# Sheet1.net
KiCad netlist of a schematic drawn in Altium Designer
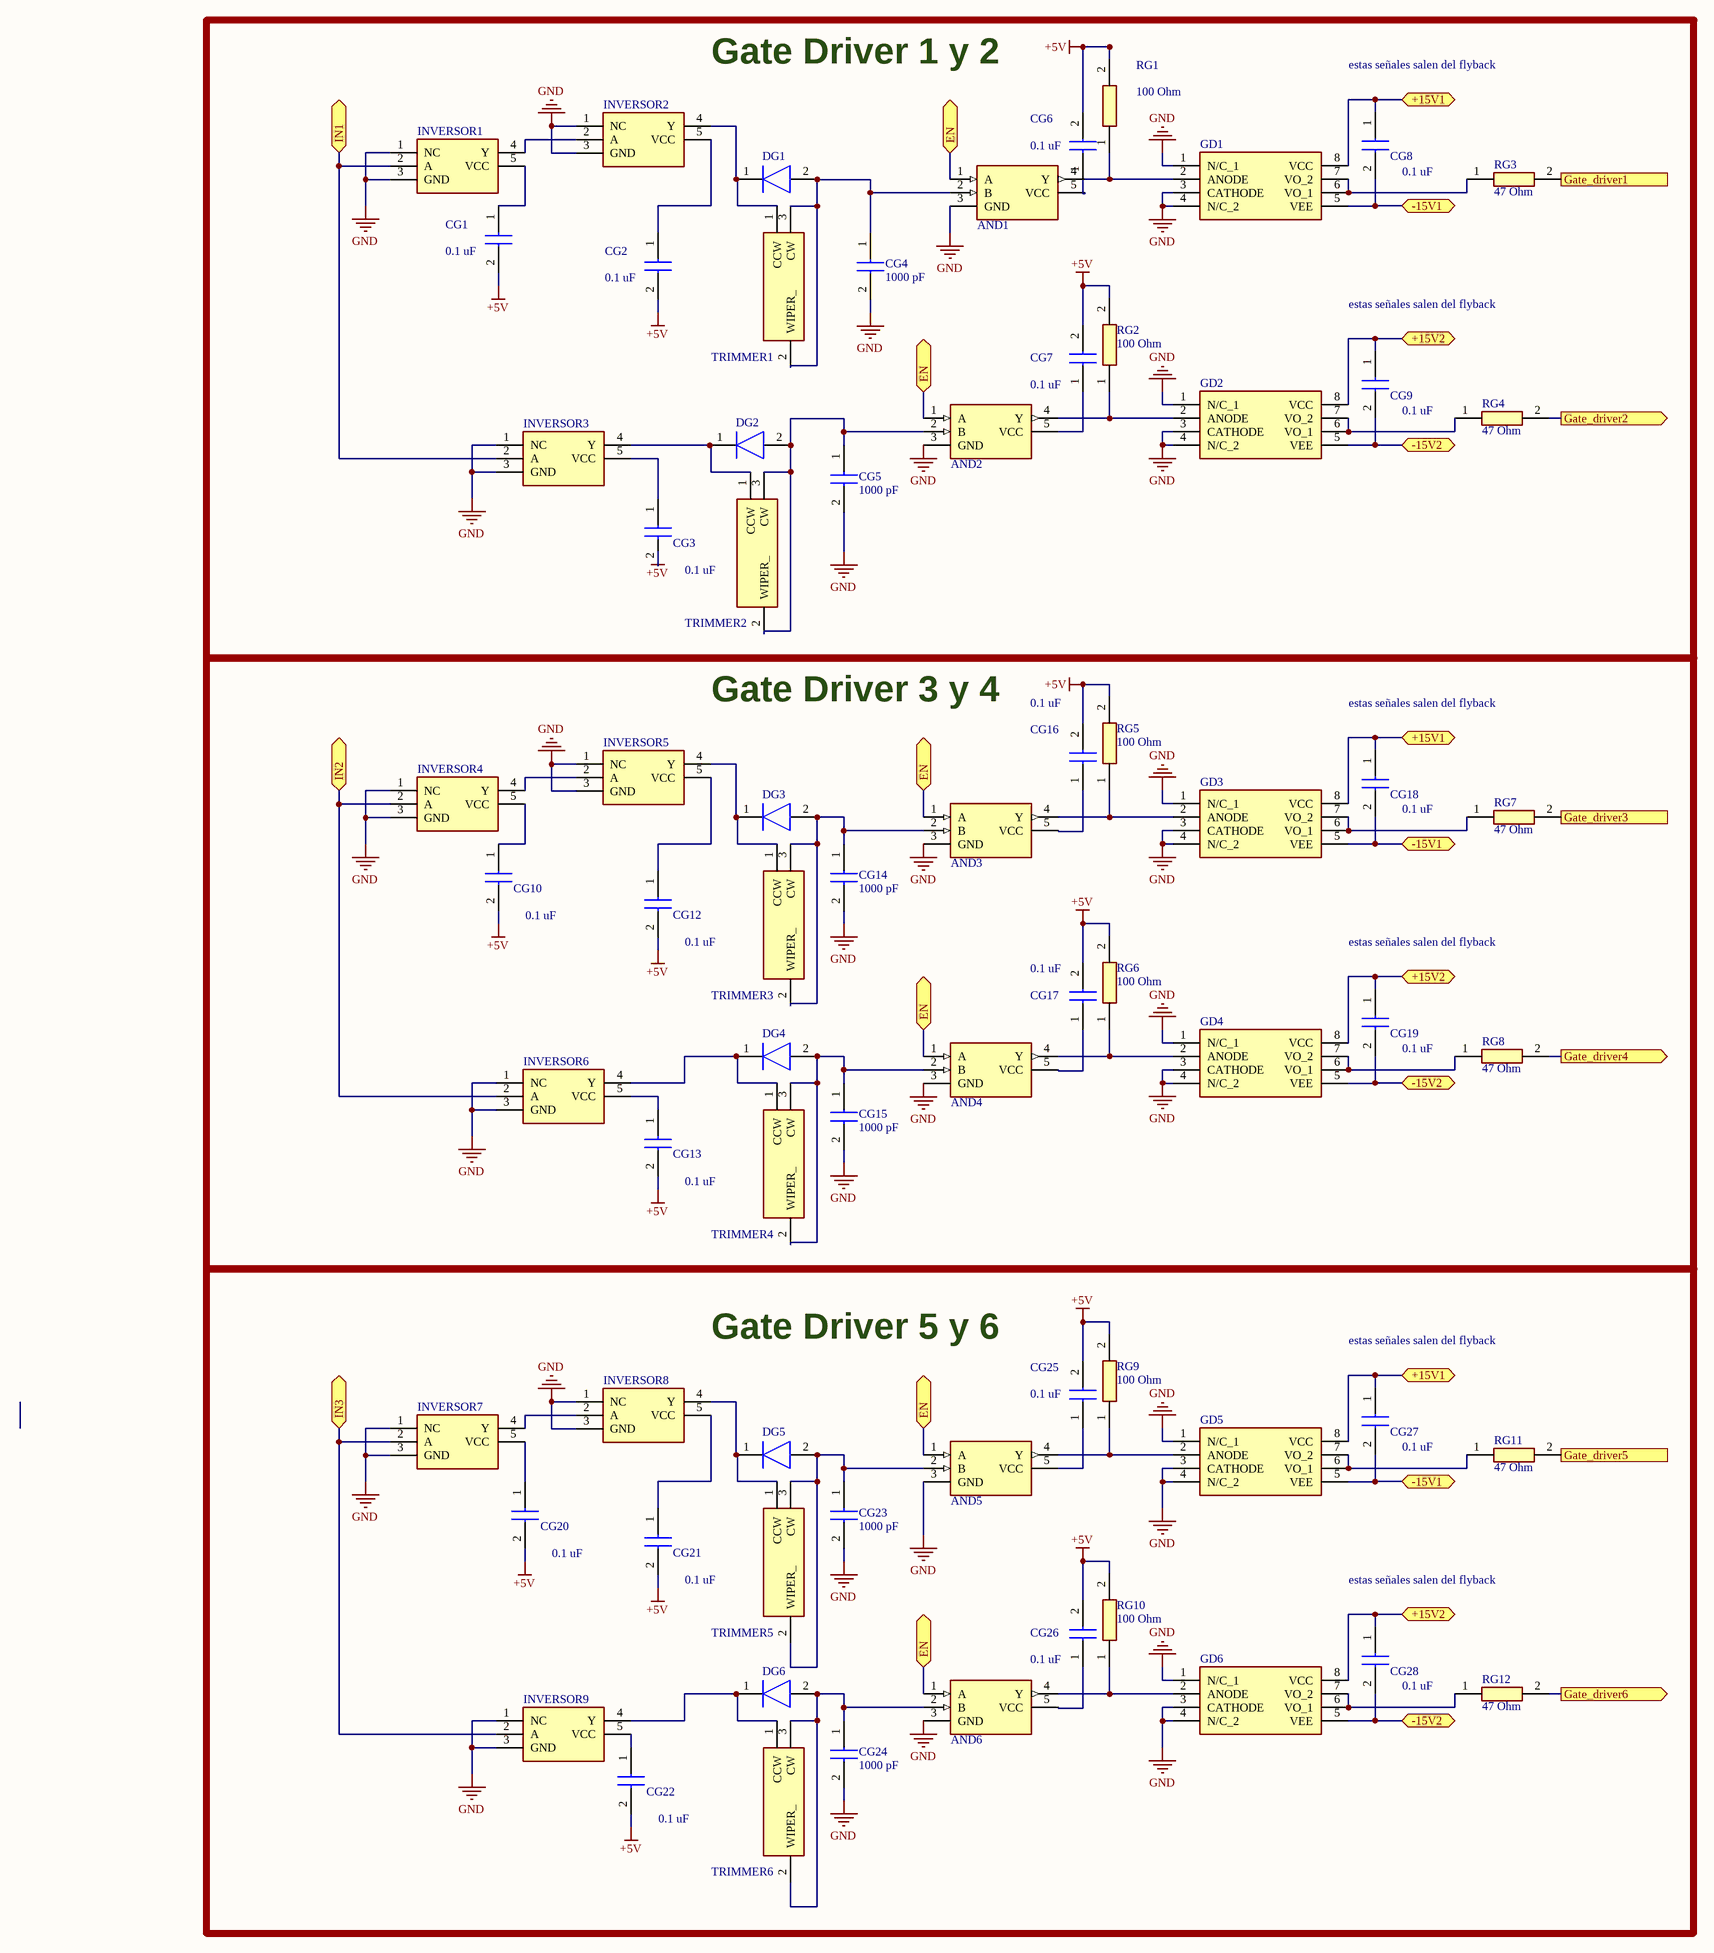
[diagram p0: Sheet1.SchDoc]

(export (version "E")
  (design (tool "Eeschema 10.0.6"))
  (components
    (comp (ref "AND1")
      (value "SN74AHC1G09DCKR")
      (footprint "jasiel:SOT65P210X110-5N")
      (fields (field (name "MANUFACTURER") "Texas Instruments"))
      (libsource (lib "sch jasiel") (part "SN74AHC1G09DCKR"))
    )
    (comp (ref "AND2")
      (value "SN74AHC1G09DCKR")
      (footprint "jasiel:SOT65P210X110-5N")
      (fields (field (name "MANUFACTURER") "Texas Instruments"))
      (libsource (lib "sch jasiel") (part "SN74AHC1G09DCKR"))
    )
    (comp (ref "AND3")
      (value "SN74AHC1G09DCKR")
      (footprint "jasiel:SOT65P210X110-5N")
      (fields (field (name "MANUFACTURER") "Texas Instruments"))
      (libsource (lib "sch jasiel") (part "SN74AHC1G09DCKR"))
    )
    (comp (ref "AND4")
      (value "SN74AHC1G09DCKR")
      (footprint "jasiel:SOT65P210X110-5N")
      (fields (field (name "MANUFACTURER") "Texas Instruments"))
      (libsource (lib "sch jasiel") (part "SN74AHC1G09DCKR"))
    )
    (comp (ref "AND5")
      (value "SN74AHC1G09DCKR")
      (footprint "jasiel:SOT65P210X110-5N")
      (fields (field (name "MANUFACTURER") "Texas Instruments"))
      (libsource (lib "sch jasiel") (part "SN74AHC1G09DCKR"))
    )
    (comp (ref "AND6")
      (value "SN74AHC1G09DCKR")
      (footprint "jasiel:SOT65P210X110-5N")
      (fields (field (name "MANUFACTURER") "Texas Instruments"))
      (libsource (lib "sch jasiel") (part "SN74AHC1G09DCKR"))
    )
    (comp (ref "CG1")
      (value "0.1 uF")
      (footprint "SamacSys:CAPC2012X94N")
      (description "Multilayer Ceramic Capacitors MLCC - SMD/SMT 16V .1uF X7R 0805 10%")
      (fields
        (field (name "MANUFACTURER_PART_NUMBER") "0805YC104KAT2A")
        (field (name "MOUSER PART NUMBER") "581-0805YC104K")
      )
      (libsource (lib "*") (part "0805YC104KAT2A"))
    )
    (comp (ref "CG2")
      (value "0.1 uF")
      (footprint "SamacSys:CAPC2012X94N")
      (description "Multilayer Ceramic Capacitors MLCC - SMD/SMT 16V .1uF X7R 0805 10%")
      (fields
        (field (name "MANUFACTURER_PART_NUMBER") "0805YC104KAT2A")
        (field (name "MOUSER PART NUMBER") "581-0805YC104K")
      )
      (libsource (lib "*") (part "0805YC104KAT2A"))
    )
    (comp (ref "CG3")
      (value "0.1 uF")
      (footprint "SamacSys:CAPC2012X94N")
      (description "Multilayer Ceramic Capacitors MLCC - SMD/SMT 16V .1uF X7R 0805 10%")
      (fields
        (field (name "MANUFACTURER_PART_NUMBER") "0805YC104KAT2A")
        (field (name "MOUSER PART NUMBER") "581-0805YC104K")
      )
      (libsource (lib "*") (part "0805YC104KAT2A"))
    )
    (comp (ref "CG4")
      (value "1000 pF")
      (footprint "SamacSys:CAPC2012X98N")
      (description "Multilayer Ceramic Capacitors MLCC - SMD/SMT 25volts 1000pF 10% X7R")
      (fields
        (field (name "MANUFACTURER_PART_NUMBER") "C0805Y102K3RACTU")
        (field (name "MOUSER PART NUMBER") "80-C0805Y102K3R")
      )
      (libsource (lib "sch jasiel") (part "C0805Y102K3RACTU"))
    )
    (comp (ref "CG5")
      (value "1000 pF")
      (footprint "SamacSys:CAPC2012X98N")
      (description "Multilayer Ceramic Capacitors MLCC - SMD/SMT 25volts 1000pF 10% X7R")
      (fields
        (field (name "MANUFACTURER_PART_NUMBER") "C0805Y102K3RACTU")
        (field (name "MOUSER PART NUMBER") "80-C0805Y102K3R")
      )
      (libsource (lib "sch jasiel") (part "C0805Y102K3RACTU"))
    )
    (comp (ref "CG6")
      (value "0.1 uF")
      (footprint "SamacSys:CAPC2012X94N")
      (description "Multilayer Ceramic Capacitors MLCC - SMD/SMT 16V .1uF X7R 0805 10%")
      (fields
        (field (name "MANUFACTURER_PART_NUMBER") "0805YC104KAT2A")
        (field (name "MOUSER PART NUMBER") "581-0805YC104K")
      )
      (libsource (lib "*") (part "0805YC104KAT2A"))
    )
    (comp (ref "CG7")
      (value "0.1 uF")
      (footprint "SamacSys:CAPC2012X94N")
      (description "Multilayer Ceramic Capacitors MLCC - SMD/SMT 16V .1uF X7R 0805 10%")
      (fields
        (field (name "MANUFACTURER_PART_NUMBER") "0805YC104KAT2A")
        (field (name "MOUSER PART NUMBER") "581-0805YC104K")
      )
      (libsource (lib "*") (part "0805YC104KAT2A"))
    )
    (comp (ref "CG8")
      (value "0.1 uF")
      (footprint "SamacSys:CAPC2012X94N")
      (description "Multilayer Ceramic Capacitors MLCC - SMD/SMT 16V .1uF X7R 0805 10%")
      (fields
        (field (name "MANUFACTURER_PART_NUMBER") "0805YC104KAT2A")
        (field (name "MOUSER PART NUMBER") "581-0805YC104K")
      )
      (libsource (lib "*") (part "0805YC104KAT2A"))
    )
    (comp (ref "CG9")
      (value "0.1 uF")
      (footprint "SamacSys:CAPC2012X94N")
      (description "Multilayer Ceramic Capacitors MLCC - SMD/SMT 16V .1uF X7R 0805 10%")
      (fields
        (field (name "MANUFACTURER_PART_NUMBER") "0805YC104KAT2A")
        (field (name "MOUSER PART NUMBER") "581-0805YC104K")
      )
      (libsource (lib "*") (part "0805YC104KAT2A"))
    )
    (comp (ref "CG10")
      (value "0.1 uF")
      (footprint "SamacSys:CAPC2012X94N")
      (description "Multilayer Ceramic Capacitors MLCC - SMD/SMT 16V .1uF X7R 0805 10%")
      (fields
        (field (name "MANUFACTURER_PART_NUMBER") "0805YC104KAT2A")
        (field (name "MOUSER PART NUMBER") "581-0805YC104K")
      )
      (libsource (lib "*") (part "0805YC104KAT2A"))
    )
    (comp (ref "CG12")
      (value "0.1 uF")
      (footprint "SamacSys:CAPC2012X94N")
      (description "Multilayer Ceramic Capacitors MLCC - SMD/SMT 16V .1uF X7R 0805 10%")
      (fields
        (field (name "MANUFACTURER_PART_NUMBER") "0805YC104KAT2A")
        (field (name "MOUSER PART NUMBER") "581-0805YC104K")
      )
      (libsource (lib "*") (part "0805YC104KAT2A"))
    )
    (comp (ref "CG13")
      (value "0.1 uF")
      (footprint "SamacSys:CAPC2012X94N")
      (description "Multilayer Ceramic Capacitors MLCC - SMD/SMT 16V .1uF X7R 0805 10%")
      (fields
        (field (name "MANUFACTURER_PART_NUMBER") "0805YC104KAT2A")
        (field (name "MOUSER PART NUMBER") "581-0805YC104K")
      )
      (libsource (lib "*") (part "0805YC104KAT2A"))
    )
    (comp (ref "CG14")
      (value "1000 pF")
      (footprint "SamacSys:CAPC2012X98N")
      (description "Multilayer Ceramic Capacitors MLCC - SMD/SMT 25volts 1000pF 10% X7R")
      (fields
        (field (name "MANUFACTURER_PART_NUMBER") "C0805Y102K3RACTU")
        (field (name "MOUSER PART NUMBER") "80-C0805Y102K3R")
      )
      (libsource (lib "sch jasiel") (part "C0805Y102K3RACTU"))
    )
    (comp (ref "CG15")
      (value "1000 pF")
      (footprint "SamacSys:CAPC2012X98N")
      (description "Multilayer Ceramic Capacitors MLCC - SMD/SMT 25volts 1000pF 10% X7R")
      (fields
        (field (name "MANUFACTURER_PART_NUMBER") "C0805Y102K3RACTU")
        (field (name "MOUSER PART NUMBER") "80-C0805Y102K3R")
      )
      (libsource (lib "sch jasiel") (part "C0805Y102K3RACTU"))
    )
    (comp (ref "CG16")
      (value "0.1 uF")
      (footprint "SamacSys:CAPC2012X94N")
      (description "Multilayer Ceramic Capacitors MLCC - SMD/SMT 16V .1uF X7R 0805 10%")
      (fields
        (field (name "MANUFACTURER_PART_NUMBER") "0805YC104KAT2A")
        (field (name "MOUSER PART NUMBER") "581-0805YC104K")
      )
      (libsource (lib "*") (part "0805YC104KAT2A"))
    )
    (comp (ref "CG17")
      (value "0.1 uF")
      (footprint "SamacSys:CAPC2012X94N")
      (description "Multilayer Ceramic Capacitors MLCC - SMD/SMT 16V .1uF X7R 0805 10%")
      (fields
        (field (name "MANUFACTURER_PART_NUMBER") "0805YC104KAT2A")
        (field (name "MOUSER PART NUMBER") "581-0805YC104K")
      )
      (libsource (lib "*") (part "0805YC104KAT2A"))
    )
    (comp (ref "CG18")
      (value "0.1 uF")
      (footprint "SamacSys:CAPC2012X94N")
      (description "Multilayer Ceramic Capacitors MLCC - SMD/SMT 16V .1uF X7R 0805 10%")
      (fields
        (field (name "MANUFACTURER_PART_NUMBER") "0805YC104KAT2A")
        (field (name "MOUSER PART NUMBER") "581-0805YC104K")
      )
      (libsource (lib "*") (part "0805YC104KAT2A"))
    )
    (comp (ref "CG19")
      (value "0.1 uF")
      (footprint "SamacSys:CAPC2012X94N")
      (description "Multilayer Ceramic Capacitors MLCC - SMD/SMT 16V .1uF X7R 0805 10%")
      (fields
        (field (name "MANUFACTURER_PART_NUMBER") "0805YC104KAT2A")
        (field (name "MOUSER PART NUMBER") "581-0805YC104K")
      )
      (libsource (lib "*") (part "0805YC104KAT2A"))
    )
    (comp (ref "CG20")
      (value "0.1 uF")
      (footprint "SamacSys:CAPC2012X94N")
      (description "Multilayer Ceramic Capacitors MLCC - SMD/SMT 16V .1uF X7R 0805 10%")
      (fields
        (field (name "MANUFACTURER_PART_NUMBER") "0805YC104KAT2A")
        (field (name "MOUSER PART NUMBER") "581-0805YC104K")
      )
      (libsource (lib "*") (part "0805YC104KAT2A"))
    )
    (comp (ref "CG21")
      (value "0.1 uF")
      (footprint "SamacSys:CAPC2012X94N")
      (description "Multilayer Ceramic Capacitors MLCC - SMD/SMT 16V .1uF X7R 0805 10%")
      (fields
        (field (name "MANUFACTURER_PART_NUMBER") "0805YC104KAT2A")
        (field (name "MOUSER PART NUMBER") "581-0805YC104K")
      )
      (libsource (lib "*") (part "0805YC104KAT2A"))
    )
    (comp (ref "CG22")
      (value "0.1 uF")
      (footprint "SamacSys:CAPC2012X94N")
      (description "Multilayer Ceramic Capacitors MLCC - SMD/SMT 16V .1uF X7R 0805 10%")
      (fields
        (field (name "MANUFACTURER_PART_NUMBER") "0805YC104KAT2A")
        (field (name "MOUSER PART NUMBER") "581-0805YC104K")
      )
      (libsource (lib "*") (part "0805YC104KAT2A"))
    )
    (comp (ref "CG23")
      (value "1000 pF")
      (footprint "SamacSys:CAPC2012X98N")
      (description "Multilayer Ceramic Capacitors MLCC - SMD/SMT 25volts 1000pF 10% X7R")
      (fields
        (field (name "MANUFACTURER_PART_NUMBER") "C0805Y102K3RACTU")
        (field (name "MOUSER PART NUMBER") "80-C0805Y102K3R")
      )
      (libsource (lib "sch jasiel") (part "C0805Y102K3RACTU"))
    )
    (comp (ref "CG24")
      (value "1000 pF")
      (footprint "SamacSys:CAPC2012X98N")
      (description "Multilayer Ceramic Capacitors MLCC - SMD/SMT 25volts 1000pF 10% X7R")
      (fields
        (field (name "MANUFACTURER_PART_NUMBER") "C0805Y102K3RACTU")
        (field (name "MOUSER PART NUMBER") "80-C0805Y102K3R")
      )
      (libsource (lib "sch jasiel") (part "C0805Y102K3RACTU"))
    )
    (comp (ref "CG25")
      (value "0.1 uF")
      (footprint "SamacSys:CAPC2012X94N")
      (description "Multilayer Ceramic Capacitors MLCC - SMD/SMT 16V .1uF X7R 0805 10%")
      (fields
        (field (name "MANUFACTURER_PART_NUMBER") "0805YC104KAT2A")
        (field (name "MOUSER PART NUMBER") "581-0805YC104K")
      )
      (libsource (lib "*") (part "0805YC104KAT2A"))
    )
    (comp (ref "CG26")
      (value "0.1 uF")
      (footprint "SamacSys:CAPC2012X94N")
      (description "Multilayer Ceramic Capacitors MLCC - SMD/SMT 16V .1uF X7R 0805 10%")
      (fields
        (field (name "MANUFACTURER_PART_NUMBER") "0805YC104KAT2A")
        (field (name "MOUSER PART NUMBER") "581-0805YC104K")
      )
      (libsource (lib "*") (part "0805YC104KAT2A"))
    )
    (comp (ref "CG27")
      (value "0.1 uF")
      (footprint "SamacSys:CAPC2012X94N")
      (description "Multilayer Ceramic Capacitors MLCC - SMD/SMT 16V .1uF X7R 0805 10%")
      (fields
        (field (name "MANUFACTURER_PART_NUMBER") "0805YC104KAT2A")
        (field (name "MOUSER PART NUMBER") "581-0805YC104K")
      )
      (libsource (lib "*") (part "0805YC104KAT2A"))
    )
    (comp (ref "CG28")
      (value "0.1 uF")
      (footprint "SamacSys:CAPC2012X94N")
      (description "Multilayer Ceramic Capacitors MLCC - SMD/SMT 16V .1uF X7R 0805 10%")
      (fields
        (field (name "MANUFACTURER_PART_NUMBER") "0805YC104KAT2A")
        (field (name "MOUSER PART NUMBER") "581-0805YC104K")
      )
      (libsource (lib "*") (part "0805YC104KAT2A"))
    )
    (comp (ref "DG1")
      (value "BAS85-GS08")
      (footprint "jasiel:BAQ33GS08")
      (description "VISHAY - BAS85-GS08 - Small Signal Schottky Diode, Single, 30 V, 200 mA, 800 mV, 600 mA, 125 °C")
      (fields (field (name "MANUFACTURER") "Vishay Semiconductors") (field (name "VOLTAGE") "30V"))
      (libsource (lib "sch jasiel") (part "BAS85-GS08"))
    )
    (comp (ref "DG2")
      (value "BAS85-GS08")
      (footprint "jasiel:BAQ33GS08")
      (description "VISHAY - BAS85-GS08 - Small Signal Schottky Diode, Single, 30 V, 200 mA, 800 mV, 600 mA, 125 °C")
      (fields (field (name "MANUFACTURER") "Vishay Semiconductors") (field (name "VOLTAGE") "30V"))
      (libsource (lib "sch jasiel") (part "BAS85-GS08"))
    )
    (comp (ref "DG3")
      (value "BAS85-GS08")
      (footprint "jasiel:BAQ33GS08")
      (description "VISHAY - BAS85-GS08 - Small Signal Schottky Diode, Single, 30 V, 200 mA, 800 mV, 600 mA, 125 °C")
      (fields (field (name "MANUFACTURER") "Vishay Semiconductors") (field (name "VOLTAGE") "30V"))
      (libsource (lib "sch jasiel") (part "BAS85-GS08"))
    )
    (comp (ref "DG4")
      (value "BAS85-GS08")
      (footprint "jasiel:BAQ33GS08")
      (description "VISHAY - BAS85-GS08 - Small Signal Schottky Diode, Single, 30 V, 200 mA, 800 mV, 600 mA, 125 °C")
      (fields (field (name "MANUFACTURER") "Vishay Semiconductors") (field (name "VOLTAGE") "30V"))
      (libsource (lib "sch jasiel") (part "BAS85-GS08"))
    )
    (comp (ref "DG5")
      (value "BAS85-GS08")
      (footprint "jasiel:BAQ33GS08")
      (description "VISHAY - BAS85-GS08 - Small Signal Schottky Diode, Single, 30 V, 200 mA, 800 mV, 600 mA, 125 °C")
      (fields (field (name "MANUFACTURER") "Vishay Semiconductors") (field (name "VOLTAGE") "30V"))
      (libsource (lib "sch jasiel") (part "BAS85-GS08"))
    )
    (comp (ref "DG6")
      (value "BAS85-GS08")
      (footprint "jasiel:BAQ33GS08")
      (description "VISHAY - BAS85-GS08 - Small Signal Schottky Diode, Single, 30 V, 200 mA, 800 mV, 600 mA, 125 °C")
      (fields (field (name "MANUFACTURER") "Vishay Semiconductors") (field (name "VOLTAGE") "30V"))
      (libsource (lib "sch jasiel") (part "BAS85-GS08"))
    )
    (comp (ref "GD1")
      (value "HCPL-3120")
      (footprint "jasiel:DIP762W65P254L965H470Q8N")
      (description "Optocoupler Drive Push-Pull 1-CH 30V 1500V 8-Pin PDIP")
      (fields
        (field (name "MOUSER2 PART NUMBER") "630-HCPL-3120")
        (field (name "MANUFACTURER") "Broadcom Avago")
      )
      (libsource (lib "sch jasiel") (part "HCPL-3120"))
    )
    (comp (ref "GD2")
      (value "HCPL-3120")
      (footprint "jasiel:DIP762W65P254L965H470Q8N")
      (description "Optocoupler Drive Push-Pull 1-CH 30V 1500V 8-Pin PDIP")
      (fields
        (field (name "MOUSER2 PART NUMBER") "630-HCPL-3120")
        (field (name "MANUFACTURER") "Broadcom Avago")
      )
      (libsource (lib "sch jasiel") (part "HCPL-3120"))
    )
    (comp (ref "GD3")
      (value "HCPL-3120")
      (footprint "jasiel:DIP762W65P254L965H470Q8N")
      (description "Optocoupler Drive Push-Pull 1-CH 30V 1500V 8-Pin PDIP")
      (fields
        (field (name "MOUSER2 PART NUMBER") "630-HCPL-3120")
        (field (name "MANUFACTURER") "Broadcom Avago")
      )
      (libsource (lib "sch jasiel") (part "HCPL-3120"))
    )
    (comp (ref "GD4")
      (value "HCPL-3120")
      (footprint "jasiel:DIP762W65P254L965H470Q8N")
      (description "Optocoupler Drive Push-Pull 1-CH 30V 1500V 8-Pin PDIP")
      (fields
        (field (name "MOUSER2 PART NUMBER") "630-HCPL-3120")
        (field (name "MANUFACTURER") "Broadcom Avago")
      )
      (libsource (lib "sch jasiel") (part "HCPL-3120"))
    )
    (comp (ref "GD5")
      (value "HCPL-3120")
      (footprint "jasiel:DIP762W65P254L965H470Q8N")
      (description "Optocoupler Drive Push-Pull 1-CH 30V 1500V 8-Pin PDIP")
      (fields
        (field (name "MOUSER2 PART NUMBER") "630-HCPL-3120")
        (field (name "MANUFACTURER") "Broadcom Avago")
      )
      (libsource (lib "sch jasiel") (part "HCPL-3120"))
    )
    (comp (ref "GD6")
      (value "HCPL-3120")
      (footprint "jasiel:DIP762W65P254L965H470Q8N")
      (description "Optocoupler Drive Push-Pull 1-CH 30V 1500V 8-Pin PDIP")
      (fields
        (field (name "MOUSER2 PART NUMBER") "630-HCPL-3120")
        (field (name "MANUFACTURER") "Broadcom Avago")
      )
      (libsource (lib "sch jasiel") (part "HCPL-3120"))
    )
    (comp (ref "INVERSOR1")
      (value "SN74AHC1G14DRLR")
      (footprint "SamacSys:SOTFL50P160X60-5N")
      (description "IC INVERTER SCHMITT 1CH SOT5")
      (fields
        (field (name "MOUSER2 PART NUMBER") "595-SN74AHC1G14DRLR")
        (field (name "MANUFACTURER") "Texas Instruments")
      )
      (libsource (lib "sch jasiel") (part "SN74AHC1G14DRLR"))
    )
    (comp (ref "INVERSOR2")
      (value "SN74AHC1G14DRLR")
      (footprint "SamacSys:SOTFL50P160X60-5N")
      (description "IC INVERTER SCHMITT 1CH SOT5")
      (fields
        (field (name "MOUSER2 PART NUMBER") "595-SN74AHC1G14DRLR")
        (field (name "MANUFACTURER") "Texas Instruments")
      )
      (libsource (lib "sch jasiel") (part "SN74AHC1G14DRLR"))
    )
    (comp (ref "INVERSOR3")
      (value "SN74AHC1G14DRLR")
      (footprint "SamacSys:SOTFL50P160X60-5N")
      (description "IC INVERTER SCHMITT 1CH SOT5")
      (fields
        (field (name "MOUSER2 PART NUMBER") "595-SN74AHC1G14DRLR")
        (field (name "MANUFACTURER") "Texas Instruments")
      )
      (libsource (lib "sch jasiel") (part "SN74AHC1G14DRLR"))
    )
    (comp (ref "INVERSOR4")
      (value "SN74AHC1G14DRLR")
      (footprint "SamacSys:SOTFL50P160X60-5N")
      (description "IC INVERTER SCHMITT 1CH SOT5")
      (fields
        (field (name "MOUSER2 PART NUMBER") "595-SN74AHC1G14DRLR")
        (field (name "MANUFACTURER") "Texas Instruments")
      )
      (libsource (lib "sch jasiel") (part "SN74AHC1G14DRLR"))
    )
    (comp (ref "INVERSOR5")
      (value "SN74AHC1G14DRLR")
      (footprint "SamacSys:SOTFL50P160X60-5N")
      (description "IC INVERTER SCHMITT 1CH SOT5")
      (fields
        (field (name "MOUSER2 PART NUMBER") "595-SN74AHC1G14DRLR")
        (field (name "MANUFACTURER") "Texas Instruments")
      )
      (libsource (lib "sch jasiel") (part "SN74AHC1G14DRLR"))
    )
    (comp (ref "INVERSOR6")
      (value "SN74AHC1G14DRLR")
      (footprint "SamacSys:SOTFL50P160X60-5N")
      (description "IC INVERTER SCHMITT 1CH SOT5")
      (fields
        (field (name "MOUSER2 PART NUMBER") "595-SN74AHC1G14DRLR")
        (field (name "MANUFACTURER") "Texas Instruments")
      )
      (libsource (lib "sch jasiel") (part "SN74AHC1G14DRLR"))
    )
    (comp (ref "INVERSOR7")
      (value "SN74AHC1G14DRLR")
      (footprint "SamacSys:SOTFL50P160X60-5N")
      (description "IC INVERTER SCHMITT 1CH SOT5")
      (fields
        (field (name "MOUSER2 PART NUMBER") "595-SN74AHC1G14DRLR")
        (field (name "MANUFACTURER") "Texas Instruments")
      )
      (libsource (lib "sch jasiel") (part "SN74AHC1G14DRLR"))
    )
    (comp (ref "INVERSOR8")
      (value "SN74AHC1G14DRLR")
      (footprint "SamacSys:SOTFL50P160X60-5N")
      (description "IC INVERTER SCHMITT 1CH SOT5")
      (fields
        (field (name "MOUSER2 PART NUMBER") "595-SN74AHC1G14DRLR")
        (field (name "MANUFACTURER") "Texas Instruments")
      )
      (libsource (lib "sch jasiel") (part "SN74AHC1G14DRLR"))
    )
    (comp (ref "INVERSOR9")
      (value "SN74AHC1G14DRLR")
      (footprint "SamacSys:SOTFL50P160X60-5N")
      (description "IC INVERTER SCHMITT 1CH SOT5")
      (fields
        (field (name "MOUSER2 PART NUMBER") "595-SN74AHC1G14DRLR")
        (field (name "MANUFACTURER") "Texas Instruments")
      )
      (libsource (lib "sch jasiel") (part "SN74AHC1G14DRLR"))
    )
    (comp (ref "RG1")
      (value "100 Ohm")
      (footprint "jasiel:RESC1608X55N")
      (description "YAGEO - RC0603JR-13100RL - RES, THICK FILM, 100R, 5%, 0.1W, 0603")
      (fields
        (field (name "MANUFACTURER_PART_NUMBER") "RC0603JR-13100RL")
        (field (name "MANUFACTURER") "Yageo")
      )
      (libsource (lib "") (part "RC0603JR-13100RL_1"))
    )
    (comp (ref "RG2")
      (value "100 Ohm")
      (footprint "jasiel:RESC1608X55N")
      (description "YAGEO - RC0603JR-13100RL - RES, THICK FILM, 100R, 5%, 0.1W, 0603")
      (fields
        (field (name "MANUFACTURER_PART_NUMBER") "RC0603JR-13100RL")
        (field (name "MANUFACTURER") "Yageo")
      )
      (libsource (lib "") (part "RC0603JR-13100RL_1"))
    )
    (comp (ref "RG3")
      (value "47 Ohm")
      (footprint "jasiel:RESC1608X55N")
      (description "Res Thick Film 1218 47 Ohm 5% 1W ±200ppm/C Pad SMD Automotive T/R")
      (fields
        (field (name "MANUFACTURER_PART_NUMBER") "RC0603JR-13100RL")
        (field (name "MANUFACTURER") "Yageo")
      )
      (libsource (lib "sch jasiel") (part "RC0603JR-13100RL"))
    )
    (comp (ref "RG4")
      (value "47 Ohm")
      (footprint "jasiel:RESC1608X55N")
      (description "Res Thick Film 1218 47 Ohm 5% 1W ±200ppm/C Pad SMD Automotive T/R")
      (fields
        (field (name "MANUFACTURER_PART_NUMBER") "RC0603JR-13100RL")
        (field (name "MANUFACTURER") "Yageo")
      )
      (libsource (lib "sch jasiel") (part "RC0603JR-13100RL"))
    )
    (comp (ref "RG5")
      (value "100 Ohm")
      (footprint "jasiel:RESC1608X55N")
      (description "YAGEO - RC0603JR-13100RL - RES, THICK FILM, 100R, 5%, 0.1W, 0603")
      (fields
        (field (name "MANUFACTURER_PART_NUMBER") "RC0603JR-13100RL")
        (field (name "MANUFACTURER") "Yageo")
      )
      (libsource (lib "") (part "RC0603JR-13100RL_1"))
    )
    (comp (ref "RG6")
      (value "100 Ohm")
      (footprint "jasiel:RESC1608X55N")
      (description "YAGEO - RC0603JR-13100RL - RES, THICK FILM, 100R, 5%, 0.1W, 0603")
      (fields
        (field (name "MANUFACTURER_PART_NUMBER") "RC0603JR-13100RL")
        (field (name "MANUFACTURER") "Yageo")
      )
      (libsource (lib "") (part "RC0603JR-13100RL_1"))
    )
    (comp (ref "RG7")
      (value "47 Ohm")
      (footprint "jasiel:RESC1608X55N")
      (description "Res Thick Film 1218 47 Ohm 5% 1W ±200ppm/C Pad SMD Automotive T/R")
      (fields
        (field (name "MANUFACTURER_PART_NUMBER") "RC0603JR-13100RL")
        (field (name "MANUFACTURER") "Yageo")
      )
      (libsource (lib "sch jasiel") (part "RC0603JR-13100RL"))
    )
    (comp (ref "RG8")
      (value "47 Ohm")
      (footprint "jasiel:RESC1608X55N")
      (description "Res Thick Film 1218 47 Ohm 5% 1W ±200ppm/C Pad SMD Automotive T/R")
      (fields
        (field (name "MANUFACTURER_PART_NUMBER") "RC0603JR-13100RL")
        (field (name "MANUFACTURER") "Yageo")
      )
      (libsource (lib "sch jasiel") (part "RC0603JR-13100RL"))
    )
    (comp (ref "RG9")
      (value "100 Ohm")
      (footprint "jasiel:RESC1608X55N")
      (description "YAGEO - RC0603JR-13100RL - RES, THICK FILM, 100R, 5%, 0.1W, 0603")
      (fields
        (field (name "MANUFACTURER_PART_NUMBER") "RC0603JR-13100RL")
        (field (name "MANUFACTURER") "Yageo")
      )
      (libsource (lib "") (part "RC0603JR-13100RL_1"))
    )
    (comp (ref "RG10")
      (value "100 Ohm")
      (footprint "jasiel:RESC1608X55N")
      (description "YAGEO - RC0603JR-13100RL - RES, THICK FILM, 100R, 5%, 0.1W, 0603")
      (fields
        (field (name "MANUFACTURER_PART_NUMBER") "RC0603JR-13100RL")
        (field (name "MANUFACTURER") "Yageo")
      )
      (libsource (lib "") (part "RC0603JR-13100RL_1"))
    )
    (comp (ref "RG11")
      (value "47 Ohm")
      (footprint "jasiel:RESC1608X55N")
      (description "Res Thick Film 1218 47 Ohm 5% 1W ±200ppm/C Pad SMD Automotive T/R")
      (fields
        (field (name "MANUFACTURER_PART_NUMBER") "RC0603JR-13100RL")
        (field (name "MANUFACTURER") "Yageo")
      )
      (libsource (lib "sch jasiel") (part "RC0603JR-13100RL"))
    )
    (comp (ref "RG12")
      (value "47 Ohm")
      (footprint "jasiel:RESC1608X55N")
      (description "Res Thick Film 1218 47 Ohm 5% 1W ±200ppm/C Pad SMD Automotive T/R")
      (fields
        (field (name "MANUFACTURER_PART_NUMBER") "RC0603JR-13100RL")
        (field (name "MANUFACTURER") "Yageo")
      )
      (libsource (lib "sch jasiel") (part "RC0603JR-13100RL"))
    )
    (comp (ref "TRIMMER1")
      (value "ST-4ETB203")
      (footprint "SamacSys:ST4ETB203")
      (description "TRIMMER 20K OHM 0.25W SMD")
      (fields
        (field (name "MANUFACTURER") "Nidec Copal")
        (field (name "MANUFACTURER PART NUMBER") "ST4ETB203")
      )
      (libsource (lib "sch jasiel") (part "ST-4ETB203"))
    )
    (comp (ref "TRIMMER2")
      (value "ST-4ETB203")
      (footprint "SamacSys:ST4ETB203")
      (description "TRIMMER 20K OHM 0.25W SMD")
      (fields
        (field (name "MANUFACTURER") "Nidec Copal")
        (field (name "MANUFACTURER PART NUMBER") "ST4ETB203")
      )
      (libsource (lib "sch jasiel") (part "ST-4ETB203"))
    )
    (comp (ref "TRIMMER3")
      (value "ST-4ETB203")
      (footprint "SamacSys:ST4ETB203")
      (description "TRIMMER 20K OHM 0.25W SMD")
      (fields
        (field (name "MANUFACTURER") "Nidec Copal")
        (field (name "MANUFACTURER PART NUMBER") "ST4ETB203")
      )
      (libsource (lib "sch jasiel") (part "ST-4ETB203"))
    )
    (comp (ref "TRIMMER4")
      (value "ST-4ETB203")
      (footprint "SamacSys:ST4ETB203")
      (description "TRIMMER 20K OHM 0.25W SMD")
      (fields
        (field (name "MANUFACTURER") "Nidec Copal")
        (field (name "MANUFACTURER PART NUMBER") "ST4ETB203")
      )
      (libsource (lib "sch jasiel") (part "ST-4ETB203"))
    )
    (comp (ref "TRIMMER5")
      (value "ST-4ETB203")
      (footprint "SamacSys:ST4ETB203")
      (description "TRIMMER 20K OHM 0.25W SMD")
      (fields
        (field (name "MANUFACTURER") "Nidec Copal")
        (field (name "MANUFACTURER PART NUMBER") "ST4ETB203")
      )
      (libsource (lib "sch jasiel") (part "ST-4ETB203"))
    )
    (comp (ref "TRIMMER6")
      (value "ST-4ETB203")
      (footprint "SamacSys:ST4ETB203")
      (description "TRIMMER 20K OHM 0.25W SMD")
      (fields
        (field (name "MANUFACTURER") "Nidec Copal")
        (field (name "MANUFACTURER PART NUMBER") "ST4ETB203")
      )
      (libsource (lib "sch jasiel") (part "ST-4ETB203"))
    )
  )
  (nets
    (net (code "1") (name "+5V") (class "Default")
      (node (ref "CG1") (pin "2") (pinfunction "2_2") (pintype "passive"))
      (node (ref "CG10") (pin "2") (pinfunction "2_2") (pintype "passive"))
      (node (ref "CG12") (pin "2") (pinfunction "2_2") (pintype "passive"))
      (node (ref "CG13") (pin "2") (pinfunction "2_2") (pintype "passive"))
      (node (ref "CG16") (pin "2") (pinfunction "2_2") (pintype "passive"))
      (node (ref "CG17") (pin "2") (pinfunction "2_2") (pintype "passive"))
      (node (ref "CG2") (pin "2") (pinfunction "2_2") (pintype "passive"))
      (node (ref "CG20") (pin "2") (pinfunction "2_2") (pintype "passive"))
      (node (ref "CG21") (pin "2") (pinfunction "2_2") (pintype "passive"))
      (node (ref "CG22") (pin "2") (pinfunction "2_2") (pintype "passive"))
      (node (ref "CG25") (pin "2") (pinfunction "2_2") (pintype "passive"))
      (node (ref "CG26") (pin "2") (pinfunction "2_2") (pintype "passive"))
      (node (ref "CG3") (pin "2") (pinfunction "2_2") (pintype "passive"))
      (node (ref "CG6") (pin "2") (pinfunction "2_2") (pintype "passive"))
      (node (ref "CG7") (pin "2") (pinfunction "2_2") (pintype "passive"))
      (node (ref "RG1") (pin "2") (pinfunction "2_2") (pintype "passive"))
      (node (ref "RG10") (pin "2") (pinfunction "2_2") (pintype "passive"))
      (node (ref "RG2") (pin "2") (pinfunction "2_2") (pintype "passive"))
      (node (ref "RG5") (pin "2") (pinfunction "2_2") (pintype "passive"))
      (node (ref "RG6") (pin "2") (pinfunction "2_2") (pintype "passive"))
      (node (ref "RG9") (pin "2") (pinfunction "2_2") (pintype "passive"))
    )
    (net (code "2") (name "/+15V1") (class "Default")
      (node (ref "CG18") (pin "1") (pinfunction "1_1") (pintype "passive"))
      (node (ref "CG27") (pin "1") (pinfunction "1_1") (pintype "passive"))
      (node (ref "CG8") (pin "1") (pinfunction "1_1") (pintype "passive"))
      (node (ref "GD1") (pin "8") (pinfunction "VCC_8") (pintype "passive"))
      (node (ref "GD3") (pin "8") (pinfunction "VCC_8") (pintype "passive"))
      (node (ref "GD5") (pin "8") (pinfunction "VCC_8") (pintype "passive"))
    )
    (net (code "3") (name "/+15V2") (class "Default")
      (node (ref "CG19") (pin "1") (pinfunction "1_1") (pintype "passive"))
      (node (ref "CG28") (pin "1") (pinfunction "1_1") (pintype "passive"))
      (node (ref "CG9") (pin "1") (pinfunction "1_1") (pintype "passive"))
      (node (ref "GD2") (pin "8") (pinfunction "VCC_8") (pintype "passive"))
      (node (ref "GD4") (pin "8") (pinfunction "VCC_8") (pintype "passive"))
      (node (ref "GD6") (pin "8") (pinfunction "VCC_8") (pintype "passive"))
    )
    (net (code "4") (name "/-15V1") (class "Default")
      (node (ref "CG18") (pin "2") (pinfunction "2_2") (pintype "passive"))
      (node (ref "CG27") (pin "2") (pinfunction "2_2") (pintype "passive"))
      (node (ref "CG8") (pin "2") (pinfunction "2_2") (pintype "passive"))
      (node (ref "GD1") (pin "5") (pinfunction "VEE_5") (pintype "passive"))
      (node (ref "GD3") (pin "5") (pinfunction "VEE_5") (pintype "passive"))
      (node (ref "GD5") (pin "5") (pinfunction "VEE_5") (pintype "passive"))
    )
    (net (code "5") (name "/-15V2") (class "Default")
      (node (ref "CG19") (pin "2") (pinfunction "2_2") (pintype "passive"))
      (node (ref "CG28") (pin "2") (pinfunction "2_2") (pintype "passive"))
      (node (ref "CG9") (pin "2") (pinfunction "2_2") (pintype "passive"))
      (node (ref "GD2") (pin "5") (pinfunction "VEE_5") (pintype "passive"))
      (node (ref "GD4") (pin "5") (pinfunction "VEE_5") (pintype "passive"))
      (node (ref "GD6") (pin "5") (pinfunction "VEE_5") (pintype "passive"))
    )
    (net (code "6") (name "/EN") (class "Default")
      (node (ref "AND1") (pin "1") (pinfunction "A_1") (pintype "input"))
      (node (ref "AND2") (pin "1") (pinfunction "A_1") (pintype "input"))
      (node (ref "AND3") (pin "1") (pinfunction "A_1") (pintype "input"))
      (node (ref "AND4") (pin "1") (pinfunction "A_1") (pintype "input"))
      (node (ref "AND5") (pin "1") (pinfunction "A_1") (pintype "input"))
      (node (ref "AND6") (pin "1") (pinfunction "A_1") (pintype "input"))
    )
    (net (code "7") (name "/Gate_driver1") (class "Default")
      (node (ref "RG3") (pin "2") (pinfunction "2_2") (pintype "passive"))
    )
    (net (code "8") (name "/Gate_driver2") (class "Default")
      (node (ref "RG4") (pin "2") (pinfunction "2_2") (pintype "passive"))
    )
    (net (code "9") (name "/Gate_driver3") (class "Default")
      (node (ref "RG7") (pin "2") (pinfunction "2_2") (pintype "passive"))
    )
    (net (code "10") (name "/Gate_driver4") (class "Default")
      (node (ref "RG8") (pin "2") (pinfunction "2_2") (pintype "passive"))
    )
    (net (code "11") (name "/Gate_driver5") (class "Default")
      (node (ref "RG11") (pin "2") (pinfunction "2_2") (pintype "passive"))
    )
    (net (code "12") (name "/Gate_driver6") (class "Default")
      (node (ref "RG12") (pin "2") (pinfunction "2_2") (pintype "passive"))
    )
    (net (code "13") (name "/IN1") (class "Default")
      (node (ref "INVERSOR1") (pin "2") (pinfunction "A_2") (pintype "passive"))
      (node (ref "INVERSOR3") (pin "2") (pinfunction "A_2") (pintype "passive"))
    )
    (net (code "14") (name "/IN2") (class "Default")
      (node (ref "INVERSOR4") (pin "2") (pinfunction "A_2") (pintype "passive"))
      (node (ref "INVERSOR6") (pin "2") (pinfunction "A_2") (pintype "passive"))
    )
    (net (code "15") (name "/IN3") (class "Default")
      (node (ref "INVERSOR7") (pin "2") (pinfunction "A_2") (pintype "passive"))
      (node (ref "INVERSOR9") (pin "2") (pinfunction "A_2") (pintype "passive"))
    )
    (net (code "16") (name "GND") (class "Default")
      (node (ref "AND1") (pin "3") (pinfunction "GND_3") (pintype "power_in"))
      (node (ref "AND2") (pin "3") (pinfunction "GND_3") (pintype "power_in"))
      (node (ref "AND3") (pin "3") (pinfunction "GND_3") (pintype "power_in"))
      (node (ref "AND4") (pin "3") (pinfunction "GND_3") (pintype "power_in"))
      (node (ref "AND5") (pin "3") (pinfunction "GND_3") (pintype "power_in"))
      (node (ref "AND6") (pin "3") (pinfunction "GND_3") (pintype "power_in"))
      (node (ref "CG14") (pin "2") (pinfunction "2_2") (pintype "passive"))
      (node (ref "CG15") (pin "2") (pinfunction "2_2") (pintype "passive"))
      (node (ref "CG23") (pin "2") (pinfunction "2_2") (pintype "passive"))
      (node (ref "CG24") (pin "2") (pinfunction "2_2") (pintype "passive"))
      (node (ref "CG4") (pin "2") (pinfunction "2_2") (pintype "passive"))
      (node (ref "CG5") (pin "2") (pinfunction "2_2") (pintype "passive"))
      (node (ref "GD1") (pin "1") (pinfunction "N/C_1_1") (pintype "passive"))
      (node (ref "GD1") (pin "3") (pinfunction "CATHODE_3") (pintype "passive"))
      (node (ref "GD1") (pin "4") (pinfunction "N/C_2_4") (pintype "passive"))
      (node (ref "GD2") (pin "1") (pinfunction "N/C_1_1") (pintype "passive"))
      (node (ref "GD2") (pin "3") (pinfunction "CATHODE_3") (pintype "passive"))
      (node (ref "GD2") (pin "4") (pinfunction "N/C_2_4") (pintype "passive"))
      (node (ref "GD3") (pin "1") (pinfunction "N/C_1_1") (pintype "passive"))
      (node (ref "GD3") (pin "3") (pinfunction "CATHODE_3") (pintype "passive"))
      (node (ref "GD3") (pin "4") (pinfunction "N/C_2_4") (pintype "passive"))
      (node (ref "GD4") (pin "1") (pinfunction "N/C_1_1") (pintype "passive"))
      (node (ref "GD4") (pin "3") (pinfunction "CATHODE_3") (pintype "passive"))
      (node (ref "GD4") (pin "4") (pinfunction "N/C_2_4") (pintype "passive"))
      (node (ref "GD5") (pin "1") (pinfunction "N/C_1_1") (pintype "passive"))
      (node (ref "GD5") (pin "3") (pinfunction "CATHODE_3") (pintype "passive"))
      (node (ref "GD5") (pin "4") (pinfunction "N/C_2_4") (pintype "passive"))
      (node (ref "GD6") (pin "1") (pinfunction "N/C_1_1") (pintype "passive"))
      (node (ref "GD6") (pin "3") (pinfunction "CATHODE_3") (pintype "passive"))
      (node (ref "GD6") (pin "4") (pinfunction "N/C_2_4") (pintype "passive"))
      (node (ref "INVERSOR1") (pin "1") (pinfunction "NC_1") (pintype "passive"))
      (node (ref "INVERSOR1") (pin "3") (pinfunction "GND_3") (pintype "passive"))
      (node (ref "INVERSOR2") (pin "1") (pinfunction "NC_1") (pintype "passive"))
      (node (ref "INVERSOR2") (pin "3") (pinfunction "GND_3") (pintype "passive"))
      (node (ref "INVERSOR3") (pin "1") (pinfunction "NC_1") (pintype "passive"))
      (node (ref "INVERSOR3") (pin "3") (pinfunction "GND_3") (pintype "passive"))
      (node (ref "INVERSOR4") (pin "1") (pinfunction "NC_1") (pintype "passive"))
      (node (ref "INVERSOR4") (pin "3") (pinfunction "GND_3") (pintype "passive"))
      (node (ref "INVERSOR5") (pin "1") (pinfunction "NC_1") (pintype "passive"))
      (node (ref "INVERSOR5") (pin "3") (pinfunction "GND_3") (pintype "passive"))
      (node (ref "INVERSOR6") (pin "1") (pinfunction "NC_1") (pintype "passive"))
      (node (ref "INVERSOR6") (pin "3") (pinfunction "GND_3") (pintype "passive"))
      (node (ref "INVERSOR7") (pin "1") (pinfunction "NC_1") (pintype "passive"))
      (node (ref "INVERSOR7") (pin "3") (pinfunction "GND_3") (pintype "passive"))
      (node (ref "INVERSOR8") (pin "1") (pinfunction "NC_1") (pintype "passive"))
      (node (ref "INVERSOR8") (pin "3") (pinfunction "GND_3") (pintype "passive"))
      (node (ref "INVERSOR9") (pin "1") (pinfunction "NC_1") (pintype "passive"))
      (node (ref "INVERSOR9") (pin "3") (pinfunction "GND_3") (pintype "passive"))
    )
    (net (code "17") (name "Net-(AND1-B)") (class "Default")
      (node (ref "AND1") (pin "2") (pinfunction "B_2") (pintype "input"))
      (node (ref "CG4") (pin "1") (pinfunction "1_1") (pintype "passive"))
      (node (ref "DG1") (pin "2") (pinfunction "A_2") (pintype "passive"))
      (node (ref "TRIMMER1") (pin "2") (pinfunction "WIPER__2") (pintype "passive"))
      (node (ref "TRIMMER1") (pin "3") (pinfunction "CW_3") (pintype "passive"))
    )
    (net (code "18") (name "Net-(AND1-VCC)") (class "Default")
      (node (ref "AND1") (pin "5") (pinfunction "VCC_5") (pintype "power_in"))
      (node (ref "CG6") (pin "1") (pinfunction "1_1") (pintype "passive"))
    )
    (net (code "19") (name "Net-(AND1-Y)") (class "Default")
      (node (ref "AND1") (pin "4") (pinfunction "Y_4") (pintype "output"))
      (node (ref "GD1") (pin "2") (pinfunction "ANODE_2") (pintype "passive"))
      (node (ref "RG1") (pin "1") (pinfunction "1_1") (pintype "passive"))
    )
    (net (code "20") (name "Net-(AND2-B)") (class "Default")
      (node (ref "AND2") (pin "2") (pinfunction "B_2") (pintype "input"))
      (node (ref "CG5") (pin "1") (pinfunction "1_1") (pintype "passive"))
      (node (ref "DG2") (pin "2") (pinfunction "A_2") (pintype "passive"))
      (node (ref "TRIMMER2") (pin "2") (pinfunction "WIPER__2") (pintype "passive"))
      (node (ref "TRIMMER2") (pin "3") (pinfunction "CW_3") (pintype "passive"))
    )
    (net (code "21") (name "Net-(AND2-VCC)") (class "Default")
      (node (ref "AND2") (pin "5") (pinfunction "VCC_5") (pintype "power_in"))
      (node (ref "CG7") (pin "1") (pinfunction "1_1") (pintype "passive"))
    )
    (net (code "22") (name "Net-(AND2-Y)") (class "Default")
      (node (ref "AND2") (pin "4") (pinfunction "Y_4") (pintype "output"))
      (node (ref "GD2") (pin "2") (pinfunction "ANODE_2") (pintype "passive"))
      (node (ref "RG2") (pin "1") (pinfunction "1_1") (pintype "passive"))
    )
    (net (code "23") (name "Net-(AND3-B)") (class "Default")
      (node (ref "AND3") (pin "2") (pinfunction "B_2") (pintype "input"))
      (node (ref "CG14") (pin "1") (pinfunction "1_1") (pintype "passive"))
      (node (ref "DG3") (pin "2") (pinfunction "A_2") (pintype "passive"))
      (node (ref "TRIMMER3") (pin "2") (pinfunction "WIPER__2") (pintype "passive"))
      (node (ref "TRIMMER3") (pin "3") (pinfunction "CW_3") (pintype "passive"))
    )
    (net (code "24") (name "Net-(AND3-VCC)") (class "Default")
      (node (ref "AND3") (pin "5") (pinfunction "VCC_5") (pintype "power_in"))
      (node (ref "CG16") (pin "1") (pinfunction "1_1") (pintype "passive"))
    )
    (net (code "25") (name "Net-(AND3-Y)") (class "Default")
      (node (ref "AND3") (pin "4") (pinfunction "Y_4") (pintype "output"))
      (node (ref "GD3") (pin "2") (pinfunction "ANODE_2") (pintype "passive"))
      (node (ref "RG5") (pin "1") (pinfunction "1_1") (pintype "passive"))
    )
    (net (code "26") (name "Net-(AND4-B)") (class "Default")
      (node (ref "AND4") (pin "2") (pinfunction "B_2") (pintype "input"))
      (node (ref "CG15") (pin "1") (pinfunction "1_1") (pintype "passive"))
      (node (ref "DG4") (pin "2") (pinfunction "A_2") (pintype "passive"))
      (node (ref "TRIMMER4") (pin "2") (pinfunction "WIPER__2") (pintype "passive"))
      (node (ref "TRIMMER4") (pin "3") (pinfunction "CW_3") (pintype "passive"))
    )
    (net (code "27") (name "Net-(AND4-VCC)") (class "Default")
      (node (ref "AND4") (pin "5") (pinfunction "VCC_5") (pintype "power_in"))
      (node (ref "CG17") (pin "1") (pinfunction "1_1") (pintype "passive"))
    )
    (net (code "28") (name "Net-(AND4-Y)") (class "Default")
      (node (ref "AND4") (pin "4") (pinfunction "Y_4") (pintype "output"))
      (node (ref "GD4") (pin "2") (pinfunction "ANODE_2") (pintype "passive"))
      (node (ref "RG6") (pin "1") (pinfunction "1_1") (pintype "passive"))
    )
    (net (code "29") (name "Net-(AND5-B)") (class "Default")
      (node (ref "AND5") (pin "2") (pinfunction "B_2") (pintype "input"))
      (node (ref "CG23") (pin "1") (pinfunction "1_1") (pintype "passive"))
      (node (ref "DG5") (pin "2") (pinfunction "A_2") (pintype "passive"))
      (node (ref "TRIMMER5") (pin "2") (pinfunction "WIPER__2") (pintype "passive"))
      (node (ref "TRIMMER5") (pin "3") (pinfunction "CW_3") (pintype "passive"))
    )
    (net (code "30") (name "Net-(AND5-VCC)") (class "Default")
      (node (ref "AND5") (pin "5") (pinfunction "VCC_5") (pintype "power_in"))
      (node (ref "CG25") (pin "1") (pinfunction "1_1") (pintype "passive"))
    )
    (net (code "31") (name "Net-(AND5-Y)") (class "Default")
      (node (ref "AND5") (pin "4") (pinfunction "Y_4") (pintype "output"))
      (node (ref "GD5") (pin "2") (pinfunction "ANODE_2") (pintype "passive"))
      (node (ref "RG9") (pin "1") (pinfunction "1_1") (pintype "passive"))
    )
    (net (code "32") (name "Net-(AND6-B)") (class "Default")
      (node (ref "AND6") (pin "2") (pinfunction "B_2") (pintype "input"))
      (node (ref "CG24") (pin "1") (pinfunction "1_1") (pintype "passive"))
      (node (ref "DG6") (pin "2") (pinfunction "A_2") (pintype "passive"))
      (node (ref "TRIMMER6") (pin "2") (pinfunction "WIPER__2") (pintype "passive"))
      (node (ref "TRIMMER6") (pin "3") (pinfunction "CW_3") (pintype "passive"))
    )
    (net (code "33") (name "Net-(AND6-VCC)") (class "Default")
      (node (ref "AND6") (pin "5") (pinfunction "VCC_5") (pintype "power_in"))
      (node (ref "CG26") (pin "1") (pinfunction "1_1") (pintype "passive"))
    )
    (net (code "34") (name "Net-(AND6-Y)") (class "Default")
      (node (ref "AND6") (pin "4") (pinfunction "Y_4") (pintype "output"))
      (node (ref "GD6") (pin "2") (pinfunction "ANODE_2") (pintype "passive"))
      (node (ref "RG10") (pin "1") (pinfunction "1_1") (pintype "passive"))
    )
    (net (code "35") (name "Net-(DG1-K)") (class "Default")
      (node (ref "DG1") (pin "1") (pinfunction "K_1") (pintype "passive"))
      (node (ref "INVERSOR2") (pin "4") (pinfunction "Y_4") (pintype "passive"))
      (node (ref "TRIMMER1") (pin "1") (pinfunction "CCW_1") (pintype "passive"))
    )
    (net (code "36") (name "Net-(DG2-K)") (class "Default")
      (node (ref "DG2") (pin "1") (pinfunction "K_1") (pintype "passive"))
      (node (ref "INVERSOR3") (pin "4") (pinfunction "Y_4") (pintype "passive"))
      (node (ref "TRIMMER2") (pin "1") (pinfunction "CCW_1") (pintype "passive"))
    )
    (net (code "37") (name "Net-(DG3-K)") (class "Default")
      (node (ref "DG3") (pin "1") (pinfunction "K_1") (pintype "passive"))
      (node (ref "INVERSOR5") (pin "4") (pinfunction "Y_4") (pintype "passive"))
      (node (ref "TRIMMER3") (pin "1") (pinfunction "CCW_1") (pintype "passive"))
    )
    (net (code "38") (name "Net-(DG4-K)") (class "Default")
      (node (ref "DG4") (pin "1") (pinfunction "K_1") (pintype "passive"))
      (node (ref "INVERSOR6") (pin "4") (pinfunction "Y_4") (pintype "passive"))
      (node (ref "TRIMMER4") (pin "1") (pinfunction "CCW_1") (pintype "passive"))
    )
    (net (code "39") (name "Net-(DG5-K)") (class "Default")
      (node (ref "DG5") (pin "1") (pinfunction "K_1") (pintype "passive"))
      (node (ref "INVERSOR8") (pin "4") (pinfunction "Y_4") (pintype "passive"))
      (node (ref "TRIMMER5") (pin "1") (pinfunction "CCW_1") (pintype "passive"))
    )
    (net (code "40") (name "Net-(DG6-K)") (class "Default")
      (node (ref "DG6") (pin "1") (pinfunction "K_1") (pintype "passive"))
      (node (ref "INVERSOR9") (pin "4") (pinfunction "Y_4") (pintype "passive"))
      (node (ref "TRIMMER6") (pin "1") (pinfunction "CCW_1") (pintype "passive"))
    )
    (net (code "41") (name "Net-(GD1-VO_1)") (class "Default")
      (node (ref "GD1") (pin "6") (pinfunction "VO_1_6") (pintype "passive"))
      (node (ref "GD1") (pin "7") (pinfunction "VO_2_7") (pintype "passive"))
      (node (ref "RG3") (pin "1") (pinfunction "1_1") (pintype "passive"))
    )
    (net (code "42") (name "Net-(GD2-VO_1)") (class "Default")
      (node (ref "GD2") (pin "6") (pinfunction "VO_1_6") (pintype "passive"))
      (node (ref "GD2") (pin "7") (pinfunction "VO_2_7") (pintype "passive"))
      (node (ref "RG4") (pin "1") (pinfunction "1_1") (pintype "passive"))
    )
    (net (code "43") (name "Net-(GD3-VO_1)") (class "Default")
      (node (ref "GD3") (pin "6") (pinfunction "VO_1_6") (pintype "passive"))
      (node (ref "GD3") (pin "7") (pinfunction "VO_2_7") (pintype "passive"))
      (node (ref "RG7") (pin "1") (pinfunction "1_1") (pintype "passive"))
    )
    (net (code "44") (name "Net-(GD4-VO_1)") (class "Default")
      (node (ref "GD4") (pin "6") (pinfunction "VO_1_6") (pintype "passive"))
      (node (ref "GD4") (pin "7") (pinfunction "VO_2_7") (pintype "passive"))
      (node (ref "RG8") (pin "1") (pinfunction "1_1") (pintype "passive"))
    )
    (net (code "45") (name "Net-(GD5-VO_1)") (class "Default")
      (node (ref "GD5") (pin "6") (pinfunction "VO_1_6") (pintype "passive"))
      (node (ref "GD5") (pin "7") (pinfunction "VO_2_7") (pintype "passive"))
      (node (ref "RG11") (pin "1") (pinfunction "1_1") (pintype "passive"))
    )
    (net (code "46") (name "Net-(GD6-VO_1)") (class "Default")
      (node (ref "GD6") (pin "6") (pinfunction "VO_1_6") (pintype "passive"))
      (node (ref "GD6") (pin "7") (pinfunction "VO_2_7") (pintype "passive"))
      (node (ref "RG12") (pin "1") (pinfunction "1_1") (pintype "passive"))
    )
    (net (code "47") (name "Net-(INVERSOR1-VCC)") (class "Default")
      (node (ref "CG1") (pin "1") (pinfunction "1_1") (pintype "passive"))
      (node (ref "INVERSOR1") (pin "5") (pinfunction "VCC_5") (pintype "passive"))
    )
    (net (code "48") (name "Net-(INVERSOR1-Y)") (class "Default")
      (node (ref "INVERSOR1") (pin "4") (pinfunction "Y_4") (pintype "passive"))
      (node (ref "INVERSOR2") (pin "2") (pinfunction "A_2") (pintype "passive"))
    )
    (net (code "49") (name "Net-(INVERSOR2-VCC)") (class "Default")
      (node (ref "CG2") (pin "1") (pinfunction "1_1") (pintype "passive"))
      (node (ref "INVERSOR2") (pin "5") (pinfunction "VCC_5") (pintype "passive"))
    )
    (net (code "50") (name "Net-(INVERSOR3-VCC)") (class "Default")
      (node (ref "CG3") (pin "1") (pinfunction "1_1") (pintype "passive"))
      (node (ref "INVERSOR3") (pin "5") (pinfunction "VCC_5") (pintype "passive"))
    )
    (net (code "51") (name "Net-(INVERSOR4-VCC)") (class "Default")
      (node (ref "CG10") (pin "1") (pinfunction "1_1") (pintype "passive"))
      (node (ref "INVERSOR4") (pin "5") (pinfunction "VCC_5") (pintype "passive"))
    )
    (net (code "52") (name "Net-(INVERSOR4-Y)") (class "Default")
      (node (ref "INVERSOR4") (pin "4") (pinfunction "Y_4") (pintype "passive"))
      (node (ref "INVERSOR5") (pin "2") (pinfunction "A_2") (pintype "passive"))
    )
    (net (code "53") (name "Net-(INVERSOR5-VCC)") (class "Default")
      (node (ref "CG12") (pin "1") (pinfunction "1_1") (pintype "passive"))
      (node (ref "INVERSOR5") (pin "5") (pinfunction "VCC_5") (pintype "passive"))
    )
    (net (code "54") (name "Net-(INVERSOR6-VCC)") (class "Default")
      (node (ref "CG13") (pin "1") (pinfunction "1_1") (pintype "passive"))
      (node (ref "INVERSOR6") (pin "5") (pinfunction "VCC_5") (pintype "passive"))
    )
    (net (code "55") (name "Net-(INVERSOR7-VCC)") (class "Default")
      (node (ref "CG20") (pin "1") (pinfunction "1_1") (pintype "passive"))
      (node (ref "INVERSOR7") (pin "5") (pinfunction "VCC_5") (pintype "passive"))
    )
    (net (code "56") (name "Net-(INVERSOR7-Y)") (class "Default")
      (node (ref "INVERSOR7") (pin "4") (pinfunction "Y_4") (pintype "passive"))
      (node (ref "INVERSOR8") (pin "2") (pinfunction "A_2") (pintype "passive"))
    )
    (net (code "57") (name "Net-(INVERSOR8-VCC)") (class "Default")
      (node (ref "CG21") (pin "1") (pinfunction "1_1") (pintype "passive"))
      (node (ref "INVERSOR8") (pin "5") (pinfunction "VCC_5") (pintype "passive"))
    )
    (net (code "58") (name "Net-(INVERSOR9-VCC)") (class "Default")
      (node (ref "CG22") (pin "1") (pinfunction "1_1") (pintype "passive"))
      (node (ref "INVERSOR9") (pin "5") (pinfunction "VCC_5") (pintype "passive"))
    )
  )
)
